# stm8sboard.net
KiCad netlist of a schematic drawn in EAGLE
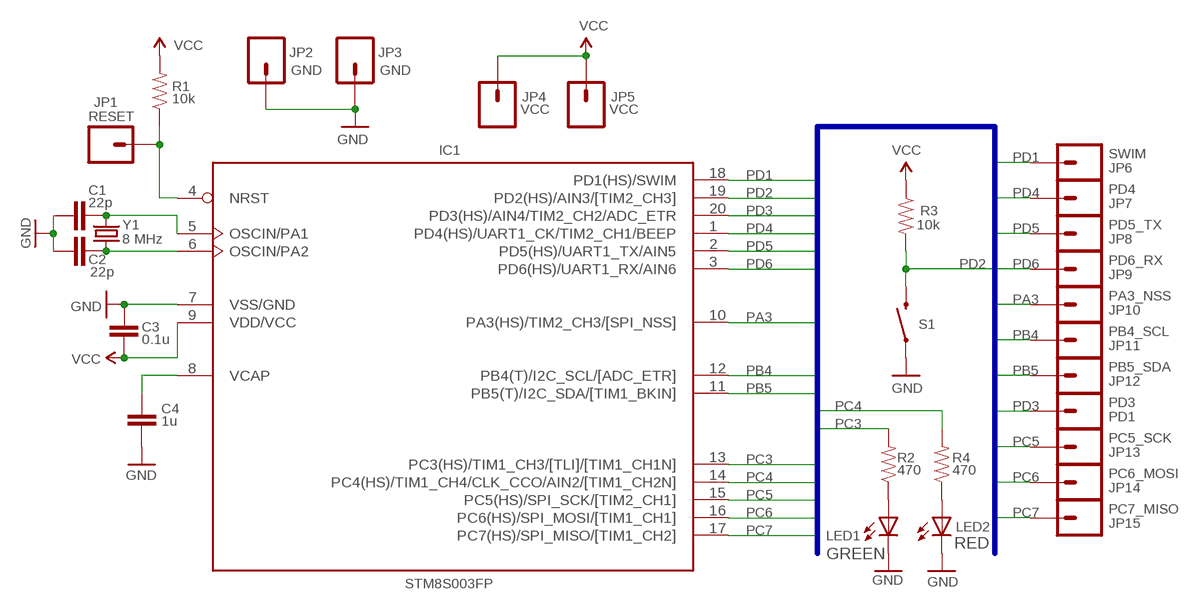
[diagram p0: schematic, sheet 1]

(export (version "E")
  (design (tool "Eeschema 10.0.6"))
  (components
    (comp (ref "C1")
      (value "22p")
      (footprint "eagle-import:0805")
      (libsource (lib "eagle-import") (part "CAP0805"))
    )
    (comp (ref "C2")
      (value "22p")
      (footprint "eagle-import:0805")
      (libsource (lib "eagle-import") (part "CAP0805"))
    )
    (comp (ref "C3")
      (value "0.1u")
      (footprint "eagle-import:0603-CAP")
      (libsource (lib "eagle-import") (part "CAP0603-CAP"))
    )
    (comp (ref "C4")
      (value "1u")
      (footprint "eagle-import:0603-CAP")
      (libsource (lib "eagle-import") (part "CAP0603-CAP"))
    )
    (comp (ref "IC1")
      (value "STM8S003FP")
      (footprint "eagle-import:TSSOP20")
      (libsource (lib "eagle-import") (part "STM8S103FP"))
    )
    (comp (ref "JP1")
      (value "RESET")
      (footprint "eagle-import:1X01")
      (libsource (lib "eagle-import") (part "M01PTH"))
    )
    (comp (ref "JP2")
      (value "GND")
      (footprint "eagle-import:1X01")
      (libsource (lib "eagle-import") (part "M01PTH"))
    )
    (comp (ref "JP3")
      (value "GND")
      (footprint "eagle-import:1X01")
      (libsource (lib "eagle-import") (part "M01PTH"))
    )
    (comp (ref "JP4")
      (value "VCC")
      (footprint "eagle-import:1X01")
      (libsource (lib "eagle-import") (part "M01PTH"))
    )
    (comp (ref "JP5")
      (value "VCC")
      (footprint "eagle-import:1X01")
      (libsource (lib "eagle-import") (part "M01PTH"))
    )
    (comp (ref "JP6")
      (value "SWIM")
      (footprint "eagle-import:1X01")
      (libsource (lib "eagle-import") (part "M01PTH"))
    )
    (comp (ref "JP7")
      (value "PD4")
      (footprint "eagle-import:1X01")
      (libsource (lib "eagle-import") (part "M01PTH"))
    )
    (comp (ref "JP8")
      (value "PD5_TX")
      (footprint "eagle-import:1X01")
      (libsource (lib "eagle-import") (part "M01PTH"))
    )
    (comp (ref "JP9")
      (value "PD6_RX")
      (footprint "eagle-import:1X01")
      (libsource (lib "eagle-import") (part "M01PTH"))
    )
    (comp (ref "JP10")
      (value "PA3_NSS")
      (footprint "eagle-import:1X01")
      (libsource (lib "eagle-import") (part "M01PTH"))
    )
    (comp (ref "JP11")
      (value "PB4_SCL")
      (footprint "eagle-import:1X01")
      (libsource (lib "eagle-import") (part "M01PTH"))
    )
    (comp (ref "JP12")
      (value "PB5_SDA")
      (footprint "eagle-import:1X01")
      (libsource (lib "eagle-import") (part "M01PTH"))
    )
    (comp (ref "JP13")
      (value "PC5_SCK")
      (footprint "eagle-import:1X01")
      (libsource (lib "eagle-import") (part "M01PTH"))
    )
    (comp (ref "JP14")
      (value "PC6_MOSI")
      (footprint "eagle-import:1X01")
      (libsource (lib "eagle-import") (part "M01PTH"))
    )
    (comp (ref "JP15")
      (value "PC7_MISO")
      (footprint "eagle-import:1X01")
      (libsource (lib "eagle-import") (part "M01PTH"))
    )
    (comp (ref "LED1")
      (value "GREEN")
      (footprint "eagle-import:LED-0603")
      (libsource (lib "eagle-import") (part "LED0603"))
    )
    (comp (ref "LED2")
      (value "RED")
      (footprint "eagle-import:LED-0603")
      (libsource (lib "eagle-import") (part "LED0603"))
    )
    (comp (ref "PD1")
      (value "PD3")
      (footprint "eagle-import:1X01")
      (libsource (lib "eagle-import") (part "M01PTH"))
    )
    (comp (ref "R1")
      (value "10k")
      (footprint "eagle-import:0805")
      (libsource (lib "eagle-import") (part "RESISTOR0805-RES"))
    )
    (comp (ref "R2")
      (value "470")
      (footprint "eagle-import:0805")
      (libsource (lib "eagle-import") (part "RESISTOR0805-RES"))
    )
    (comp (ref "R3")
      (value "10k")
      (footprint "eagle-import:0805")
      (libsource (lib "eagle-import") (part "RESISTOR0805-RES"))
    )
    (comp (ref "R4")
      (value "470")
      (footprint "eagle-import:0805")
      (libsource (lib "eagle-import") (part "RESISTOR0805-RES"))
    )
    (comp (ref "S1")
      (value "SW")
      (footprint "eagle-import:REED_SWITCH_PLASTIC")
      (libsource (lib "eagle-import") (part "SWITCH-MOMENTARY-2PTH_REED2"))
    )
    (comp (ref "Y1")
      (value "8 MHz")
      (footprint "eagle-import:HC49U-V")
      (libsource (lib "eagle-import") (part "CRYSTALHC49UV"))
    )
  )
  (nets
    (net (code "1") (name "/PA3") (class "Default")
      (node (ref "IC1") (pin "10") (pinfunction "PA3(HS)/TIM2_CH3/[SPI_NSS]_10") (pintype "bidirectional"))
      (node (ref "JP10") (pin "1") (pinfunction "1_1") (pintype "passive"))
    )
    (net (code "2") (name "/PB4") (class "Default")
      (node (ref "IC1") (pin "12") (pinfunction "PB4(T)/I2C_SCL/[ADC_ETR]_12") (pintype "bidirectional"))
      (node (ref "JP11") (pin "1") (pinfunction "1_1") (pintype "passive"))
    )
    (net (code "3") (name "/PB5") (class "Default")
      (node (ref "IC1") (pin "11") (pinfunction "PB5(T)/I2C_SDA/[TIM1_BKIN]_11") (pintype "bidirectional"))
      (node (ref "JP12") (pin "1") (pinfunction "1_1") (pintype "passive"))
    )
    (net (code "4") (name "/PC3") (class "Default")
      (node (ref "IC1") (pin "13") (pinfunction "PC3(HS)/TIM1_CH3/[TLI]/[TIM1_CH1N]_13") (pintype "bidirectional"))
      (node (ref "R2") (pin "2") (pinfunction "2_2") (pintype "passive"))
    )
    (net (code "5") (name "/PC4") (class "Default")
      (node (ref "IC1") (pin "14") (pinfunction "PC4(HS)/TIM1_CH4/CLK_CCO/AIN2/[TIM1_CH2N]_14") (pintype "bidirectional"))
      (node (ref "R4") (pin "2") (pinfunction "2_2") (pintype "passive"))
    )
    (net (code "6") (name "/PC5") (class "Default")
      (node (ref "IC1") (pin "15") (pinfunction "PC5(HS)/SPI_SCK/[TIM2_CH1]_15") (pintype "bidirectional"))
      (node (ref "JP13") (pin "1") (pinfunction "1_1") (pintype "passive"))
    )
    (net (code "7") (name "/PC6") (class "Default")
      (node (ref "IC1") (pin "16") (pinfunction "PC6(HS)/SPI_MOSI/[TIM1_CH1]_16") (pintype "bidirectional"))
      (node (ref "JP14") (pin "1") (pinfunction "1_1") (pintype "passive"))
    )
    (net (code "8") (name "/PC7") (class "Default")
      (node (ref "IC1") (pin "17") (pinfunction "PC7(HS)/SPI_MISO/[TIM1_CH2]_17") (pintype "bidirectional"))
      (node (ref "JP15") (pin "1") (pinfunction "1_1") (pintype "passive"))
    )
    (net (code "9") (name "/PD1") (class "Default")
      (node (ref "IC1") (pin "18") (pinfunction "PD1(HS)/SWIM_18") (pintype "bidirectional"))
      (node (ref "JP6") (pin "1") (pinfunction "1_1") (pintype "passive"))
    )
    (net (code "10") (name "/PD2") (class "Default")
      (node (ref "IC1") (pin "19") (pinfunction "PD2(HS)/AIN3/[TIM2_CH3]_19") (pintype "bidirectional"))
      (node (ref "R3") (pin "2") (pinfunction "2_2") (pintype "passive"))
      (node (ref "S1") (pin "P$2") (pinfunction "2_P$2") (pintype "passive"))
    )
    (net (code "11") (name "/PD3") (class "Default")
      (node (ref "IC1") (pin "20") (pinfunction "PD3(HS)/AIN4/TIM2_CH2/ADC_ETR_20") (pintype "bidirectional"))
      (node (ref "PD1") (pin "1") (pinfunction "1_1") (pintype "passive"))
    )
    (net (code "12") (name "/PD4") (class "Default")
      (node (ref "IC1") (pin "1") (pinfunction "PD4(HS)/UART1_CK/TIM2_CH1/BEEP_1") (pintype "bidirectional"))
      (node (ref "JP7") (pin "1") (pinfunction "1_1") (pintype "passive"))
    )
    (net (code "13") (name "/PD5") (class "Default")
      (node (ref "IC1") (pin "2") (pinfunction "PD5(HS)/UART1_TX/AIN5_2") (pintype "bidirectional"))
      (node (ref "JP8") (pin "1") (pinfunction "1_1") (pintype "passive"))
    )
    (net (code "14") (name "/PD6") (class "Default")
      (node (ref "IC1") (pin "3") (pinfunction "PD6(HS)/UART1_RX/AIN6_3") (pintype "bidirectional"))
      (node (ref "JP9") (pin "1") (pinfunction "1_1") (pintype "passive"))
    )
    (net (code "15") (name "GND") (class "Default")
      (node (ref "C1") (pin "1") (pinfunction "1_1") (pintype "passive"))
      (node (ref "C2") (pin "1") (pinfunction "1_1") (pintype "passive"))
      (node (ref "C3") (pin "1") (pinfunction "1_1") (pintype "passive"))
      (node (ref "C4") (pin "2") (pinfunction "2_2") (pintype "passive"))
      (node (ref "IC1") (pin "7") (pinfunction "VSS/GND_7") (pintype "power_in"))
      (node (ref "JP2") (pin "1") (pinfunction "1_1") (pintype "passive"))
      (node (ref "JP3") (pin "1") (pinfunction "1_1") (pintype "passive"))
      (node (ref "LED1") (pin "C") (pinfunction "C_C") (pintype "passive"))
      (node (ref "LED2") (pin "C") (pinfunction "C_C") (pintype "passive"))
      (node (ref "S1") (pin "P$1") (pinfunction "1_P$1") (pintype "passive"))
    )
    (net (code "16") (name "Net-(IC1-NRST)") (class "Default")
      (node (ref "IC1") (pin "4") (pinfunction "NRST_4") (pintype "bidirectional"))
      (node (ref "JP1") (pin "1") (pinfunction "1_1") (pintype "passive"))
      (node (ref "R1") (pin "1") (pinfunction "1_1") (pintype "passive"))
    )
    (net (code "17") (name "Net-(IC1-OSCIN{slash}PA1)") (class "Default")
      (node (ref "C1") (pin "2") (pinfunction "2_2") (pintype "passive"))
      (node (ref "IC1") (pin "5") (pinfunction "OSCIN/PA1_5") (pintype "bidirectional"))
      (node (ref "Y1") (pin "2") (pinfunction "2_2") (pintype "passive"))
    )
    (net (code "18") (name "Net-(IC1-OSCIN{slash}PA2)") (class "Default")
      (node (ref "C2") (pin "2") (pinfunction "2_2") (pintype "passive"))
      (node (ref "IC1") (pin "6") (pinfunction "OSCIN/PA2_6") (pintype "bidirectional"))
      (node (ref "Y1") (pin "1") (pinfunction "1_1") (pintype "passive"))
    )
    (net (code "19") (name "Net-(IC1-VCAP)") (class "Default")
      (node (ref "C4") (pin "1") (pinfunction "1_1") (pintype "passive"))
      (node (ref "IC1") (pin "8") (pinfunction "VCAP_8") (pintype "power_in"))
    )
    (net (code "20") (name "Net-(LED1-PadA)") (class "Default")
      (node (ref "LED1") (pin "A") (pinfunction "A_A") (pintype "passive"))
      (node (ref "R2") (pin "1") (pinfunction "1_1") (pintype "passive"))
    )
    (net (code "21") (name "Net-(LED2-PadA)") (class "Default")
      (node (ref "LED2") (pin "A") (pinfunction "A_A") (pintype "passive"))
      (node (ref "R4") (pin "1") (pinfunction "1_1") (pintype "passive"))
    )
    (net (code "22") (name "VCC") (class "Default")
      (node (ref "C3") (pin "2") (pinfunction "2_2") (pintype "passive"))
      (node (ref "IC1") (pin "9") (pinfunction "VDD/VCC_9") (pintype "power_in"))
      (node (ref "JP4") (pin "1") (pinfunction "1_1") (pintype "passive"))
      (node (ref "JP5") (pin "1") (pinfunction "1_1") (pintype "passive"))
      (node (ref "R1") (pin "2") (pinfunction "2_2") (pintype "passive"))
      (node (ref "R3") (pin "1") (pinfunction "1_1") (pintype "passive"))
    )
  )
)
